# sample_conn.net
KiCad netlist of a schematic drawn in Altium Designer
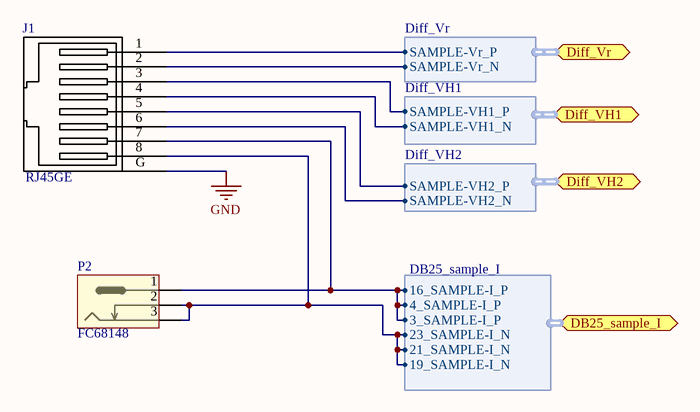
[diagram p0: sample_conn.SchDoc]

(export (version "E")
  (design (tool "Eeschema 10.0.6"))
  (components
    (comp (ref "J1")
      (value "~")
      (footprint "RJ45GE")
      (description "Connector  RJ45 8 PIN")
      (fields
        (field (name "SUPPLIER PART NUMBER 1") "RJ45GE")
        (field (name "MANUFACTURER") "NINIGI")
        (field (name "MANUFACTURER PART NUMBER") "RJ45GE")
      )
      (libsource (lib "custom_components") (part "RJ45-GENERIC"))
    )
    (comp (ref "P2")
      (value "~")
      (footprint "custom_components:dc-jack")
      (fields
        (field (name "SUPPLIER PART NUMBER 1") "FC68148")
        (field (name "MANUFACTURER") "CLIFF")
        (field (name "MANUFACTURER PART NUMBER") "DC-10A FC68148")
      )
      (libsource (lib "custom_components") (part "jackdc"))
    )
  )
  (nets
    (net (code "5") (name "/16_SAMPLE-I_P") (class "Default")
      (node (ref "J1") (pin "7") (pintype "passive"))
      (node (ref "P2") (pin "1") (pinfunction "1_1") (pintype "passive"))
    )
    (net (code "6") (name "/19_SAMPLE-I_N") (class "Default")
      (node (ref "J1") (pin "8") (pintype "passive"))
      (node (ref "P2") (pin "2") (pinfunction "2_2") (pintype "passive"))
      (node (ref "P2") (pin "3") (pinfunction "3_3") (pintype "passive"))
    )
    (net (code "7") (name "/SAMPLE-VH1_N") (class "Default") (node (ref "J1") (pin "4") (pintype "passive")))
    (net (code "8") (name "/SAMPLE-VH1_P") (class "Default") (node (ref "J1") (pin "3") (pintype "passive")))
    (net (code "9") (name "/SAMPLE-VH2_N") (class "Default") (node (ref "J1") (pin "6") (pintype "passive")))
    (net (code "10") (name "/SAMPLE-VH2_P") (class "Default") (node (ref "J1") (pin "5") (pintype "passive")))
    (net (code "11") (name "/SAMPLE-Vr_N") (class "Default") (node (ref "J1") (pin "2") (pintype "passive")))
    (net (code "12") (name "/SAMPLE-Vr_P") (class "Default") (node (ref "J1") (pin "1") (pintype "passive")))
    (net (code "17") (name "GND") (class "Default")
      (node (ref "J1") (pin "G") (pinfunction "GND_G") (pintype "passive"))
    )
  )
)
